# Accelerometers.net
KiCad netlist of a schematic drawn in Altium Designer
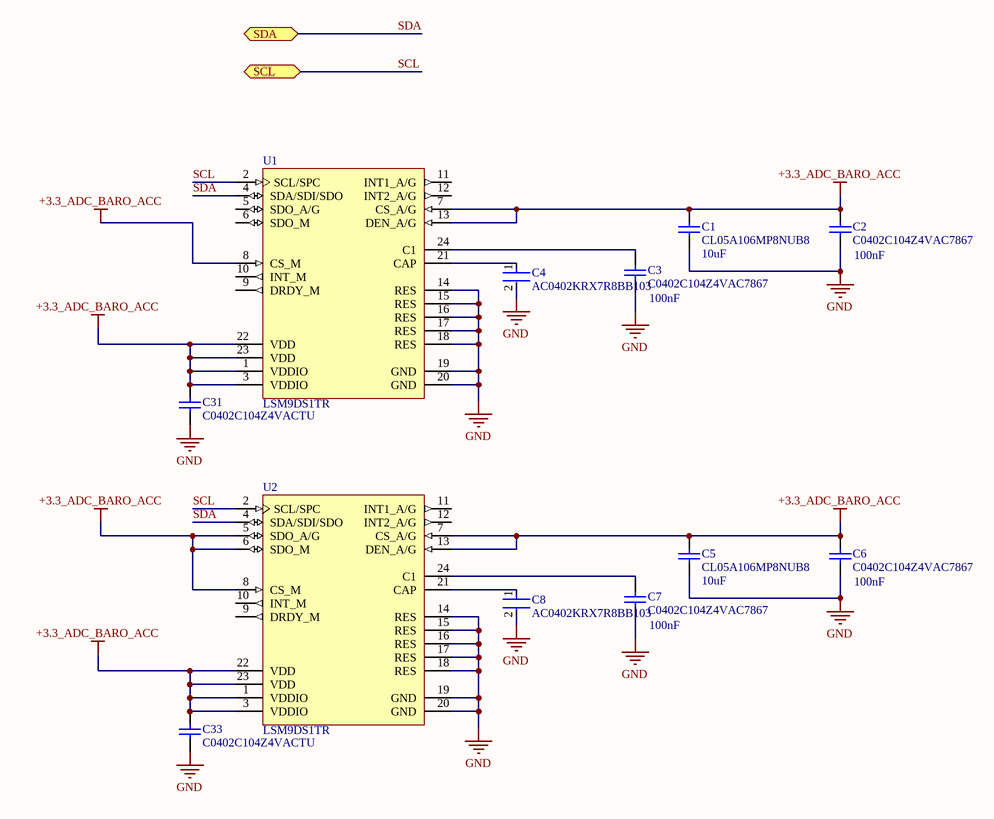
[diagram p0: Accelerometers.SchDoc]

(export (version "E")
  (design (tool "Eeschema 10.0.6"))
  (components
    (comp (ref "C1")
      (value "CL05A106MP8NUB8")
      (footprint "0402")
      (description "Capacitor")
      (fields (field (name "ALTIUM_VALUE") "10uF") (field (name "PUBLISHER") "Altium Limited"))
      (libsource (lib "Miscellaneous Devices") (part "Cap"))
    )
    (comp (ref "C2")
      (value "C0402C104Z4VAC7867")
      (footprint "CAPC1005X60X30LL05T10")
      (fields (field (name "MANUFACTURER") "Kemet") (field (name "SPEC") "100nF"))
      (libsource (lib "Altium Content Vault") (part "CAP"))
    )
    (comp (ref "C3")
      (value "C0402C104Z4VAC7867")
      (footprint "CAPC1005X60X30LL05T10")
      (fields (field (name "MANUFACTURER") "Kemet") (field (name "SPEC") "100nF"))
      (libsource (lib "Altium Content Vault") (part "CAP"))
    )
    (comp (ref "C4")
      (value "AC0402KRX7R8BB103")
      (footprint "FP-AC0402-0_5-MFG")
      (description "CAP CER 10000PF 25V X7R 0402")
      (fields
        (field (name "MANUFACTURER") "Yageo")
        (field (name "OCTOPART") "https://octopart.com/ac0402krx7r8bb103-yageo-75666114")
      )
      (libsource (lib "Altium Content Vault") (part "11868f565c42a9108669ba33697ecf6"))
    )
    (comp (ref "C5")
      (value "CL05A106MP8NUB8")
      (footprint "0402")
      (description "Capacitor")
      (fields (field (name "ALTIUM_VALUE") "10uF") (field (name "PUBLISHER") "Altium Limited"))
      (libsource (lib "Miscellaneous Devices") (part "Cap"))
    )
    (comp (ref "C6")
      (value "C0402C104Z4VAC7867")
      (footprint "CAPC1005X60X30LL05T10")
      (fields (field (name "MANUFACTURER") "Kemet") (field (name "SPEC") "100nF"))
      (libsource (lib "Altium Content Vault") (part "CAP"))
    )
    (comp (ref "C7")
      (value "C0402C104Z4VAC7867")
      (footprint "CAPC1005X60X30LL05T10")
      (fields (field (name "MANUFACTURER") "Kemet") (field (name "SPEC") "100nF"))
      (libsource (lib "Altium Content Vault") (part "CAP"))
    )
    (comp (ref "C8")
      (value "AC0402KRX7R8BB103")
      (footprint "FP-AC0402-0_5-MFG")
      (description "CAP CER 10000PF 25V X7R 0402")
      (fields
        (field (name "MANUFACTURER") "Yageo")
        (field (name "OCTOPART") "https://octopart.com/ac0402krx7r8bb103-yageo-75666114")
      )
      (libsource (lib "Altium Content Vault") (part "11868f565c42a9108669ba33697ecf6"))
    )
    (comp (ref "C31")
      (value "C0402C104Z4VACTU")
      (footprint "CAPC1005X55X30LL05T10")
      (fields (field (name "MANUFACTURER") "Kemet"))
      (libsource (lib "Altium Content Vault") (part "CAP"))
    )
    (comp (ref "C33")
      (value "C0402C104Z4VACTU")
      (footprint "CAPC1005X55X30LL05T10")
      (fields (field (name "MANUFACTURER") "Kemet"))
      (libsource (lib "Altium Content Vault") (part "CAP"))
    )
    (comp (ref "U1")
      (value "LSM9DS1TR")
      (footprint "STM-LGA-24_3500X3000X1000")
      (fields (field (name "PARTNUMBER") "LSM9DS1") (field (name "MANUFACTURER") "STMicroelectronics"))
      (libsource (lib "Altium Content Vault") (part "STM-LSM9DS1-24"))
    )
    (comp (ref "U2")
      (value "LSM9DS1TR")
      (footprint "STM-LGA-24_3500X3000X1000")
      (fields (field (name "PARTNUMBER") "LSM9DS1") (field (name "MANUFACTURER") "STMicroelectronics"))
      (libsource (lib "Altium Content Vault") (part "STM-LSM9DS1-24"))
    )
  )
  (nets
    (net (code "1") (name "+3.3_ADC_BARO_ACC") (class "Default")
      (node (ref "C1") (pin "2") (pinfunction "2_2") (pintype "passive"))
      (node (ref "C2") (pin "2") (pinfunction "2_2") (pintype "passive"))
      (node (ref "C31") (pin "2") (pinfunction "2_2") (pintype "passive"))
      (node (ref "C33") (pin "2") (pinfunction "2_2") (pintype "passive"))
      (node (ref "C5") (pin "2") (pinfunction "2_2") (pintype "passive"))
      (node (ref "C6") (pin "2") (pinfunction "2_2") (pintype "passive"))
      (node (ref "U1") (pin "1") (pinfunction "VDDIO_1") (pintype "power_in"))
      (node (ref "U1") (pin "13") (pinfunction "DEN_A/G_13") (pintype "input"))
      (node (ref "U1") (pin "22") (pinfunction "VDD_22") (pintype "power_in"))
      (node (ref "U1") (pin "23") (pinfunction "VDD_23") (pintype "power_in"))
      (node (ref "U1") (pin "3") (pinfunction "VDDIO_3") (pintype "power_in"))
      (node (ref "U1") (pin "7") (pinfunction "CS_A/G_7") (pintype "input"))
      (node (ref "U1") (pin "8") (pinfunction "CS_M_8") (pintype "input"))
      (node (ref "U2") (pin "1") (pinfunction "VDDIO_1") (pintype "power_in"))
      (node (ref "U2") (pin "13") (pinfunction "DEN_A/G_13") (pintype "input"))
      (node (ref "U2") (pin "22") (pinfunction "VDD_22") (pintype "power_in"))
      (node (ref "U2") (pin "23") (pinfunction "VDD_23") (pintype "power_in"))
      (node (ref "U2") (pin "3") (pinfunction "VDDIO_3") (pintype "power_in"))
      (node (ref "U2") (pin "5") (pinfunction "SDO_A/G_5") (pintype "bidirectional"))
      (node (ref "U2") (pin "6") (pinfunction "SDO_M_6") (pintype "bidirectional"))
      (node (ref "U2") (pin "7") (pinfunction "CS_A/G_7") (pintype "input"))
      (node (ref "U2") (pin "8") (pinfunction "CS_M_8") (pintype "input"))
    )
    (net (code "2") (name "/SCL") (class "Default")
      (node (ref "U1") (pin "2") (pinfunction "SCL/SPC_2") (pintype "input"))
      (node (ref "U2") (pin "2") (pinfunction "SCL/SPC_2") (pintype "input"))
    )
    (net (code "3") (name "/SDA") (class "Default")
      (node (ref "U1") (pin "4") (pinfunction "SDA/SDI/SDO_4") (pintype "bidirectional"))
      (node (ref "U2") (pin "4") (pinfunction "SDA/SDI/SDO_4") (pintype "bidirectional"))
    )
    (net (code "4") (name "GND") (class "Default")
      (node (ref "C1") (pin "1") (pinfunction "1_1") (pintype "passive"))
      (node (ref "C2") (pin "1") (pinfunction "1_1") (pintype "passive"))
      (node (ref "C3") (pin "1") (pinfunction "1_1") (pintype "passive"))
      (node (ref "C31") (pin "1") (pinfunction "1_1") (pintype "passive"))
      (node (ref "C33") (pin "1") (pinfunction "1_1") (pintype "passive"))
      (node (ref "C4") (pin "2") (pinfunction "2_2") (pintype "passive"))
      (node (ref "C5") (pin "1") (pinfunction "1_1") (pintype "passive"))
      (node (ref "C6") (pin "1") (pinfunction "1_1") (pintype "passive"))
      (node (ref "C7") (pin "1") (pinfunction "1_1") (pintype "passive"))
      (node (ref "C8") (pin "2") (pinfunction "2_2") (pintype "passive"))
      (node (ref "U1") (pin "14") (pinfunction "RES_14") (pintype "passive"))
      (node (ref "U1") (pin "15") (pinfunction "RES_15") (pintype "passive"))
      (node (ref "U1") (pin "16") (pinfunction "RES_16") (pintype "passive"))
      (node (ref "U1") (pin "17") (pinfunction "RES_17") (pintype "passive"))
      (node (ref "U1") (pin "18") (pinfunction "RES_18") (pintype "passive"))
      (node (ref "U1") (pin "19") (pinfunction "GND_19") (pintype "power_in"))
      (node (ref "U1") (pin "20") (pinfunction "GND_20") (pintype "power_in"))
      (node (ref "U2") (pin "14") (pinfunction "RES_14") (pintype "passive"))
      (node (ref "U2") (pin "15") (pinfunction "RES_15") (pintype "passive"))
      (node (ref "U2") (pin "16") (pinfunction "RES_16") (pintype "passive"))
      (node (ref "U2") (pin "17") (pinfunction "RES_17") (pintype "passive"))
      (node (ref "U2") (pin "18") (pinfunction "RES_18") (pintype "passive"))
      (node (ref "U2") (pin "19") (pinfunction "GND_19") (pintype "power_in"))
      (node (ref "U2") (pin "20") (pinfunction "GND_20") (pintype "power_in"))
    )
    (net (code "5") (name "Net-(U1-C1)") (class "Default")
      (node (ref "C3") (pin "2") (pinfunction "2_2") (pintype "passive"))
      (node (ref "U1") (pin "24") (pinfunction "C1_24") (pintype "passive"))
    )
    (net (code "6") (name "Net-(U1-CAP)") (class "Default")
      (node (ref "C4") (pin "1") (pinfunction "1_1") (pintype "passive"))
      (node (ref "U1") (pin "21") (pinfunction "CAP_21") (pintype "passive"))
    )
    (net (code "7") (name "Net-(U2-C1)") (class "Default")
      (node (ref "C7") (pin "2") (pinfunction "2_2") (pintype "passive"))
      (node (ref "U2") (pin "24") (pinfunction "C1_24") (pintype "passive"))
    )
    (net (code "8") (name "Net-(U2-CAP)") (class "Default")
      (node (ref "C8") (pin "1") (pinfunction "1_1") (pintype "passive"))
      (node (ref "U2") (pin "21") (pinfunction "CAP_21") (pintype "passive"))
    )
    (net (code "9") (name "unconnected-(U1-DRDY_M-Pad9)") (class "Default")
      (node (ref "U1") (pin "9") (pinfunction "DRDY_M_9") (pintype "output"))
    )
    (net (code "10") (name "unconnected-(U1-INT1_A{slash}G-Pad11)") (class "Default")
      (node (ref "U1") (pin "11") (pinfunction "INT1_A/G_11") (pintype "output"))
    )
    (net (code "11") (name "unconnected-(U1-INT2_A{slash}G-Pad12)") (class "Default")
      (node (ref "U1") (pin "12") (pinfunction "INT2_A/G_12") (pintype "output"))
    )
    (net (code "12") (name "unconnected-(U1-INT_M-Pad10)") (class "Default")
      (node (ref "U1") (pin "10") (pinfunction "INT_M_10") (pintype "output"))
    )
    (net (code "13") (name "unconnected-(U1-SDO_A{slash}G-Pad5)") (class "Default")
      (node (ref "U1") (pin "5") (pinfunction "SDO_A/G_5") (pintype "bidirectional"))
    )
    (net (code "14") (name "unconnected-(U1-SDO_M-Pad6)") (class "Default")
      (node (ref "U1") (pin "6") (pinfunction "SDO_M_6") (pintype "bidirectional"))
    )
    (net (code "15") (name "unconnected-(U2-DRDY_M-Pad9)") (class "Default")
      (node (ref "U2") (pin "9") (pinfunction "DRDY_M_9") (pintype "output"))
    )
    (net (code "16") (name "unconnected-(U2-INT1_A{slash}G-Pad11)") (class "Default")
      (node (ref "U2") (pin "11") (pinfunction "INT1_A/G_11") (pintype "output"))
    )
    (net (code "17") (name "unconnected-(U2-INT2_A{slash}G-Pad12)") (class "Default")
      (node (ref "U2") (pin "12") (pinfunction "INT2_A/G_12") (pintype "output"))
    )
    (net (code "18") (name "unconnected-(U2-INT_M-Pad10)") (class "Default")
      (node (ref "U2") (pin "10") (pinfunction "INT_M_10") (pintype "output"))
    )
  )
)
